# PIXRACER-IMU-R12.net
KiCad netlist of a schematic drawn in Altium Designer
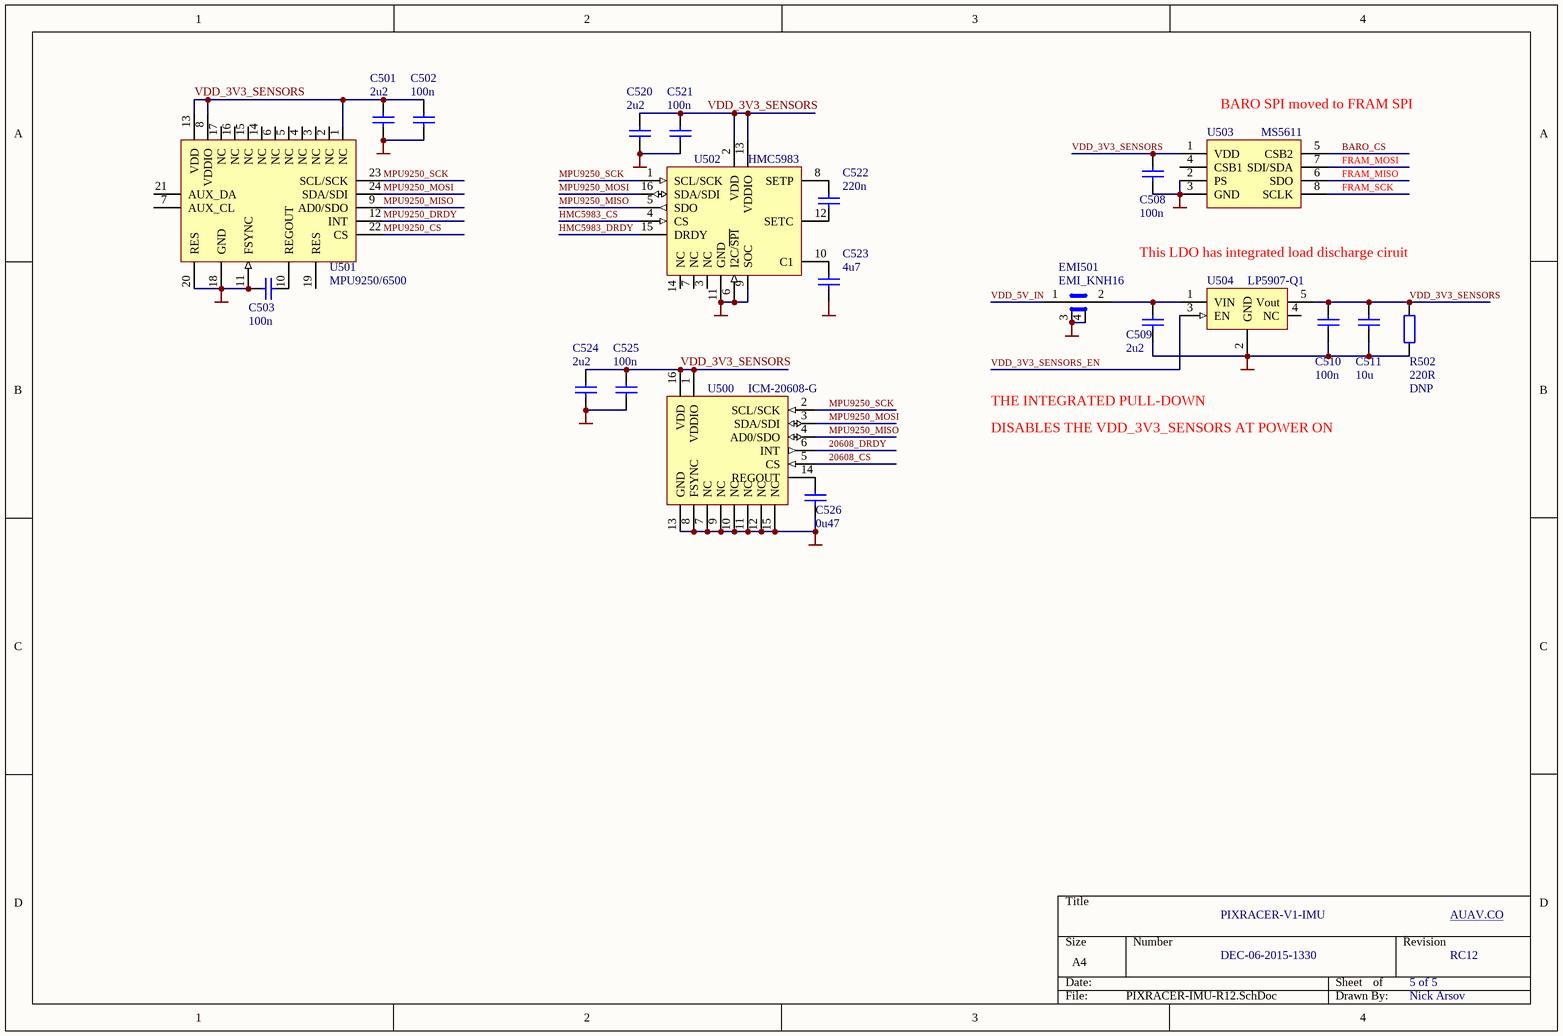
[diagram p0: PIXRACER-IMU-R12.SchDoc]

(export (version "E")
  (design (tool "Eeschema 10.0.6"))
  (components
    (comp (ref "C501")
      (value "2u2")
      (footprint "0402A")
      (description "Capacitor")
      (fields (field (name "PUBLISHER") "Altium Limited"))
      (libsource (lib "Miscellaneous Devices") (part "Cap"))
    )
    (comp (ref "C502")
      (value "100n")
      (footprint "0402A")
      (description "Capacitor")
      (fields (field (name "PUBLISHER") "Altium Limited"))
      (libsource (lib "Miscellaneous Devices") (part "Cap"))
    )
    (comp (ref "C503")
      (value "100n")
      (footprint "0402A")
      (description "Capacitor")
      (fields (field (name "PUBLISHER") "Altium Limited"))
      (libsource (lib "Miscellaneous Devices") (part "Cap"))
    )
    (comp (ref "C508")
      (value "100n")
      (footprint "0402A")
      (description "Capacitor")
      (fields (field (name "PUBLISHER") "Altium Limited"))
      (libsource (lib "Miscellaneous Devices") (part "Cap"))
    )
    (comp (ref "C509")
      (value "2u2")
      (footprint "0603A")
      (description "Capacitor")
      (fields (field (name "PUBLISHER") "Altium Limited"))
      (libsource (lib "Miscellaneous Devices") (part "Cap"))
    )
    (comp (ref "C510")
      (value "100n")
      (footprint "0603A")
      (description "Capacitor")
      (fields (field (name "PUBLISHER") "Altium Limited"))
      (libsource (lib "Miscellaneous Devices") (part "Cap"))
    )
    (comp (ref "C511")
      (value "10u")
      (footprint "0603A")
      (description "Capacitor")
      (fields (field (name "PUBLISHER") "Altium Limited"))
      (libsource (lib "Miscellaneous Devices") (part "Cap"))
    )
    (comp (ref "C520")
      (value "2u2")
      (footprint "0402A")
      (description "Capacitor")
      (fields (field (name "PUBLISHER") "Altium Limited"))
      (libsource (lib "Miscellaneous Devices") (part "Cap"))
    )
    (comp (ref "C521")
      (value "100n")
      (footprint "0402A")
      (description "Capacitor")
      (fields (field (name "PUBLISHER") "Altium Limited"))
      (libsource (lib "Miscellaneous Devices") (part "Cap"))
    )
    (comp (ref "C522")
      (value "220n")
      (footprint "0402A")
      (description "Capacitor")
      (fields (field (name "PUBLISHER") "Altium Limited"))
      (libsource (lib "Miscellaneous Devices") (part "Cap"))
    )
    (comp (ref "C523")
      (value "4u7")
      (footprint "0603A")
      (description "Capacitor")
      (fields (field (name "PUBLISHER") "Altium Limited"))
      (libsource (lib "Miscellaneous Devices") (part "Cap"))
    )
    (comp (ref "C524")
      (value "2u2")
      (footprint "0402A")
      (description "Capacitor")
      (fields (field (name "PUBLISHER") "Altium Limited"))
      (libsource (lib "Miscellaneous Devices") (part "Cap"))
    )
    (comp (ref "C525")
      (value "100n")
      (footprint "0402A")
      (description "Capacitor")
      (fields (field (name "PUBLISHER") "Altium Limited"))
      (libsource (lib "Miscellaneous Devices") (part "Cap"))
    )
    (comp (ref "C526")
      (value "0u47")
      (footprint "0402A")
      (description "Capacitor")
      (fields (field (name "PUBLISHER") "Altium Limited"))
      (libsource (lib "Miscellaneous Devices") (part "Cap"))
    )
    (comp (ref "EMI501")
      (value "EMI_KNH16")
      (footprint "EMI_KNH16_0603")
      (libsource (lib "My_Altium") (part "EMI_KNH16"))
    )
    (comp (ref "R502")
      (value "220R")
      (footprint "0402A")
      (description "Resistor")
      (fields (field (name "REM") "DNP") (field (name "PUBLISHER") "Altium Limited"))
      (libsource (lib "Miscellaneous Devices") (part "Res2"))
    )
    (comp (ref "U500")
      (value "ICM-20608-G")
      (footprint "HCLGA-16L")
      (libsource (lib "My_Altium") (part "ICM-20608-G"))
    )
    (comp (ref "U501")
      (value "MPU9250/6500")
      (footprint "QFN24_3x3")
      (libsource (lib "My_Altium") (part "MPU6500"))
    )
    (comp (ref "U502")
      (value "HMC5983")
      (footprint "HMC5883L")
      (libsource (lib "My_Altium") (part "HMC5983"))
    )
    (comp (ref "U503")
      (value "MS5611")
      (footprint "MS5611")
      (libsource (lib "My_Altium") (part "MS5611-01BA03"))
    )
    (comp (ref "U504")
      (value "LP5907-Q1")
      (footprint "SOT23-5")
      (libsource (lib "My_Altium") (part "LP5907-Q1"))
    )
  )
  (nets
    (net (code "1") (name "/20608_CS") (class "Default")
      (node (ref "U500") (pin "5") (pinfunction "CS_5") (pintype "input"))
    )
    (net (code "2") (name "/20608_DRDY") (class "Default")
      (node (ref "U500") (pin "6") (pinfunction "INT_6") (pintype "output"))
    )
    (net (code "3") (name "/BARO_CS") (class "Default")
      (node (ref "U503") (pin "5") (pinfunction "CSB2_5") (pintype "passive"))
    )
    (net (code "4") (name "/FRAM_MISO") (class "Default")
      (node (ref "U503") (pin "6") (pinfunction "SDO_6") (pintype "passive"))
    )
    (net (code "5") (name "/FRAM_MOSI") (class "Default")
      (node (ref "U503") (pin "7") (pinfunction "SDI/SDA_7") (pintype "passive"))
    )
    (net (code "6") (name "/FRAM_SCK") (class "Default")
      (node (ref "U503") (pin "8") (pinfunction "SCLK_8") (pintype "passive"))
    )
    (net (code "7") (name "/HMC5983_CS") (class "Default")
      (node (ref "U502") (pin "4") (pinfunction "CS_4") (pintype "input"))
    )
    (net (code "8") (name "/HMC5983_DRDY") (class "Default")
      (node (ref "U502") (pin "15") (pinfunction "DRDY_15") (pintype "passive"))
    )
    (net (code "9") (name "/MPU9250_CS") (class "Default")
      (node (ref "U501") (pin "22") (pinfunction "CS_22") (pintype "passive"))
    )
    (net (code "10") (name "/MPU9250_DRDY") (class "Default")
      (node (ref "U501") (pin "12") (pinfunction "INT_12") (pintype "passive"))
    )
    (net (code "11") (name "/MPU9250_MISO") (class "Default")
      (node (ref "U500") (pin "4") (pinfunction "AD0/SDO_4") (pintype "bidirectional"))
      (node (ref "U501") (pin "9") (pinfunction "AD0/SDO_9") (pintype "passive"))
      (node (ref "U502") (pin "5") (pinfunction "SDO_5") (pintype "output"))
    )
    (net (code "12") (name "/MPU9250_MOSI") (class "Default")
      (node (ref "U500") (pin "3") (pinfunction "SDA/SDI_3") (pintype "bidirectional"))
      (node (ref "U501") (pin "24") (pinfunction "SDA/SDI_24") (pintype "passive"))
      (node (ref "U502") (pin "16") (pinfunction "SDA/SDI_16") (pintype "bidirectional"))
    )
    (net (code "13") (name "/MPU9250_SCK") (class "Default")
      (node (ref "U500") (pin "2") (pinfunction "SCL/SCK_2") (pintype "input"))
      (node (ref "U501") (pin "23") (pinfunction "SCL/SCK_23") (pintype "passive"))
      (node (ref "U502") (pin "1") (pinfunction "SCL/SCK_1") (pintype "input"))
    )
    (net (code "14") (name "/VDD_3V3_SENSORS") (class "Default")
      (node (ref "C501") (pin "2") (pinfunction "2_2") (pintype "passive"))
      (node (ref "C502") (pin "2") (pinfunction "2_2") (pintype "passive"))
      (node (ref "C508") (pin "2") (pinfunction "2_2") (pintype "passive"))
      (node (ref "C510") (pin "2") (pinfunction "2_2") (pintype "passive"))
      (node (ref "C511") (pin "2") (pinfunction "2_2") (pintype "passive"))
      (node (ref "C520") (pin "2") (pinfunction "2_2") (pintype "passive"))
      (node (ref "C521") (pin "2") (pinfunction "2_2") (pintype "passive"))
      (node (ref "C524") (pin "2") (pinfunction "2_2") (pintype "passive"))
      (node (ref "C525") (pin "2") (pinfunction "2_2") (pintype "passive"))
      (node (ref "R502") (pin "2") (pinfunction "2_2") (pintype "passive"))
      (node (ref "U500") (pin "1") (pinfunction "VDDIO_1") (pintype "power_in"))
      (node (ref "U500") (pin "16") (pinfunction "VDD_16") (pintype "power_in"))
      (node (ref "U501") (pin "1") (pinfunction "NC_1") (pintype "passive"))
      (node (ref "U501") (pin "13") (pinfunction "VDD_13") (pintype "power_in"))
      (node (ref "U501") (pin "8") (pinfunction "VDDIO_8") (pintype "power_in"))
      (node (ref "U502") (pin "13") (pinfunction "VDDIO_13") (pintype "power_in"))
      (node (ref "U502") (pin "2") (pinfunction "VDD_2") (pintype "power_in"))
      (node (ref "U503") (pin "1") (pinfunction "VDD_1") (pintype "power_in"))
      (node (ref "U504") (pin "5") (pinfunction "Vout_5") (pintype "power_in"))
    )
    (net (code "15") (name "/VDD_3V3_SENSORS_EN") (class "Default")
      (node (ref "U504") (pin "3") (pinfunction "EN_3") (pintype "input"))
    )
    (net (code "16") (name "/VDD_5V_IN") (class "Default")
      (node (ref "EMI501") (pin "1") (pinfunction "L1_1") (pintype "passive"))
    )
    (net (code "17") (name "GND") (class "Default")
      (node (ref "C501") (pin "1") (pinfunction "1_1") (pintype "passive"))
      (node (ref "C502") (pin "1") (pinfunction "1_1") (pintype "passive"))
      (node (ref "C503") (pin "1") (pinfunction "1_1") (pintype "passive"))
      (node (ref "C508") (pin "1") (pinfunction "1_1") (pintype "passive"))
      (node (ref "C509") (pin "1") (pinfunction "1_1") (pintype "passive"))
      (node (ref "C510") (pin "1") (pinfunction "1_1") (pintype "passive"))
      (node (ref "C511") (pin "1") (pinfunction "1_1") (pintype "passive"))
      (node (ref "C520") (pin "1") (pinfunction "1_1") (pintype "passive"))
      (node (ref "C521") (pin "1") (pinfunction "1_1") (pintype "passive"))
      (node (ref "C523") (pin "1") (pinfunction "1_1") (pintype "passive"))
      (node (ref "C524") (pin "1") (pinfunction "1_1") (pintype "passive"))
      (node (ref "C525") (pin "1") (pinfunction "1_1") (pintype "passive"))
      (node (ref "C526") (pin "1") (pinfunction "1_1") (pintype "passive"))
      (node (ref "EMI501") (pin "3") (pinfunction "G_3") (pintype "power_in"))
      (node (ref "EMI501") (pin "4") (pinfunction "G_4") (pintype "passive"))
      (node (ref "R502") (pin "1") (pinfunction "1_1") (pintype "passive"))
      (node (ref "U500") (pin "10") (pinfunction "NC_10") (pintype "passive"))
      (node (ref "U500") (pin "11") (pinfunction "NC_11") (pintype "passive"))
      (node (ref "U500") (pin "12") (pinfunction "NC_12") (pintype "passive"))
      (node (ref "U500") (pin "13") (pinfunction "GND_13") (pintype "power_in"))
      (node (ref "U500") (pin "15") (pinfunction "NC_15") (pintype "passive"))
      (node (ref "U500") (pin "7") (pinfunction "NC_7") (pintype "passive"))
      (node (ref "U500") (pin "8") (pinfunction "FSYNC_8") (pintype "passive"))
      (node (ref "U500") (pin "9") (pinfunction "NC_9") (pintype "passive"))
      (node (ref "U501") (pin "11") (pinfunction "FSYNC_11") (pintype "input"))
      (node (ref "U501") (pin "18") (pinfunction "GND_18") (pintype "power_in"))
      (node (ref "U501") (pin "20") (pinfunction "RES_20") (pintype "passive"))
      (node (ref "U502") (pin "11") (pinfunction "GND_11") (pintype "power_in"))
      (node (ref "U502") (pin "6") (pinfunction "I2C/~{SPI}_6") (pintype "input"))
      (node (ref "U502") (pin "9") (pinfunction "SOC_9") (pintype "power_in"))
      (node (ref "U503") (pin "2") (pinfunction "PS_2") (pintype "passive"))
      (node (ref "U503") (pin "3") (pinfunction "GND_3") (pintype "power_in"))
      (node (ref "U504") (pin "2") (pinfunction "GND_2") (pintype "power_in"))
    )
    (net (code "18") (name "Net-(EMI501-L2)") (class "Default")
      (node (ref "C509") (pin "2") (pinfunction "2_2") (pintype "passive"))
      (node (ref "EMI501") (pin "2") (pinfunction "L2_2") (pintype "passive"))
      (node (ref "U504") (pin "1") (pinfunction "VIN_1") (pintype "power_in"))
    )
    (net (code "19") (name "Net-(U500-REGOUT)") (class "Default")
      (node (ref "C526") (pin "2") (pinfunction "2_2") (pintype "passive"))
      (node (ref "U500") (pin "14") (pinfunction "REGOUT_14") (pintype "passive"))
    )
    (net (code "20") (name "Net-(U501-REGOUT)") (class "Default")
      (node (ref "C503") (pin "2") (pinfunction "2_2") (pintype "passive"))
      (node (ref "U501") (pin "10") (pinfunction "REGOUT_10") (pintype "passive"))
    )
    (net (code "21") (name "Net-(U502-C1)") (class "Default")
      (node (ref "C523") (pin "2") (pinfunction "2_2") (pintype "passive"))
      (node (ref "U502") (pin "10") (pinfunction "C1_10") (pintype "passive"))
    )
    (net (code "22") (name "Net-(U502-SETC)") (class "Default")
      (node (ref "C522") (pin "1") (pinfunction "1_1") (pintype "passive"))
      (node (ref "U502") (pin "12") (pinfunction "SETC_12") (pintype "passive"))
    )
    (net (code "23") (name "Net-(U502-SETP)") (class "Default")
      (node (ref "C522") (pin "2") (pinfunction "2_2") (pintype "passive"))
      (node (ref "U502") (pin "8") (pinfunction "SETP_8") (pintype "passive"))
    )
    (net (code "24") (name "unconnected-(U501-AUX_CL-Pad7)") (class "Default")
      (node (ref "U501") (pin "7") (pinfunction "AUX_CL_7") (pintype "passive"))
    )
    (net (code "25") (name "unconnected-(U501-AUX_DA-Pad21)") (class "Default")
      (node (ref "U501") (pin "21") (pinfunction "AUX_DA_21") (pintype "passive"))
    )
    (net (code "26") (name "unconnected-(U501-NC-Pad2)") (class "Default")
      (node (ref "U501") (pin "2") (pinfunction "NC_2") (pintype "passive"))
    )
    (net (code "27") (name "unconnected-(U501-NC-Pad3)") (class "Default")
      (node (ref "U501") (pin "3") (pinfunction "NC_3") (pintype "passive"))
    )
    (net (code "28") (name "unconnected-(U501-NC-Pad4)") (class "Default")
      (node (ref "U501") (pin "4") (pinfunction "NC_4") (pintype "passive"))
    )
    (net (code "29") (name "unconnected-(U501-NC-Pad5)") (class "Default")
      (node (ref "U501") (pin "5") (pinfunction "NC_5") (pintype "passive"))
    )
    (net (code "30") (name "unconnected-(U501-NC-Pad6)") (class "Default")
      (node (ref "U501") (pin "6") (pinfunction "NC_6") (pintype "passive"))
    )
    (net (code "31") (name "unconnected-(U501-NC-Pad14)") (class "Default")
      (node (ref "U501") (pin "14") (pinfunction "NC_14") (pintype "passive"))
    )
    (net (code "32") (name "unconnected-(U501-NC-Pad15)") (class "Default")
      (node (ref "U501") (pin "15") (pinfunction "NC_15") (pintype "passive"))
    )
    (net (code "33") (name "unconnected-(U501-NC-Pad16)") (class "Default")
      (node (ref "U501") (pin "16") (pinfunction "NC_16") (pintype "passive"))
    )
    (net (code "34") (name "unconnected-(U501-NC-Pad17)") (class "Default")
      (node (ref "U501") (pin "17") (pinfunction "NC_17") (pintype "passive"))
    )
    (net (code "35") (name "unconnected-(U501-RES-Pad19)") (class "Default")
      (node (ref "U501") (pin "19") (pinfunction "RES_19") (pintype "passive"))
    )
    (net (code "36") (name "unconnected-(U502-NC-Pad3)") (class "Default")
      (node (ref "U502") (pin "3") (pinfunction "NC_3") (pintype "passive"))
    )
    (net (code "37") (name "unconnected-(U502-NC-Pad7)") (class "Default")
      (node (ref "U502") (pin "7") (pinfunction "NC_7") (pintype "passive"))
    )
    (net (code "38") (name "unconnected-(U502-NC-Pad14)") (class "Default")
      (node (ref "U502") (pin "14") (pinfunction "NC_14") (pintype "passive"))
    )
    (net (code "39") (name "unconnected-(U503-CSB1-Pad4)") (class "Default")
      (node (ref "U503") (pin "4") (pinfunction "CSB1_4") (pintype "passive"))
    )
    (net (code "40") (name "unconnected-(U504-NC-Pad4)") (class "Default")
      (node (ref "U504") (pin "4") (pinfunction "NC_4") (pintype "passive"))
    )
  )
)
